# 03_-_CONTROLLER.net
KiCad netlist of a schematic drawn in Altium Designer
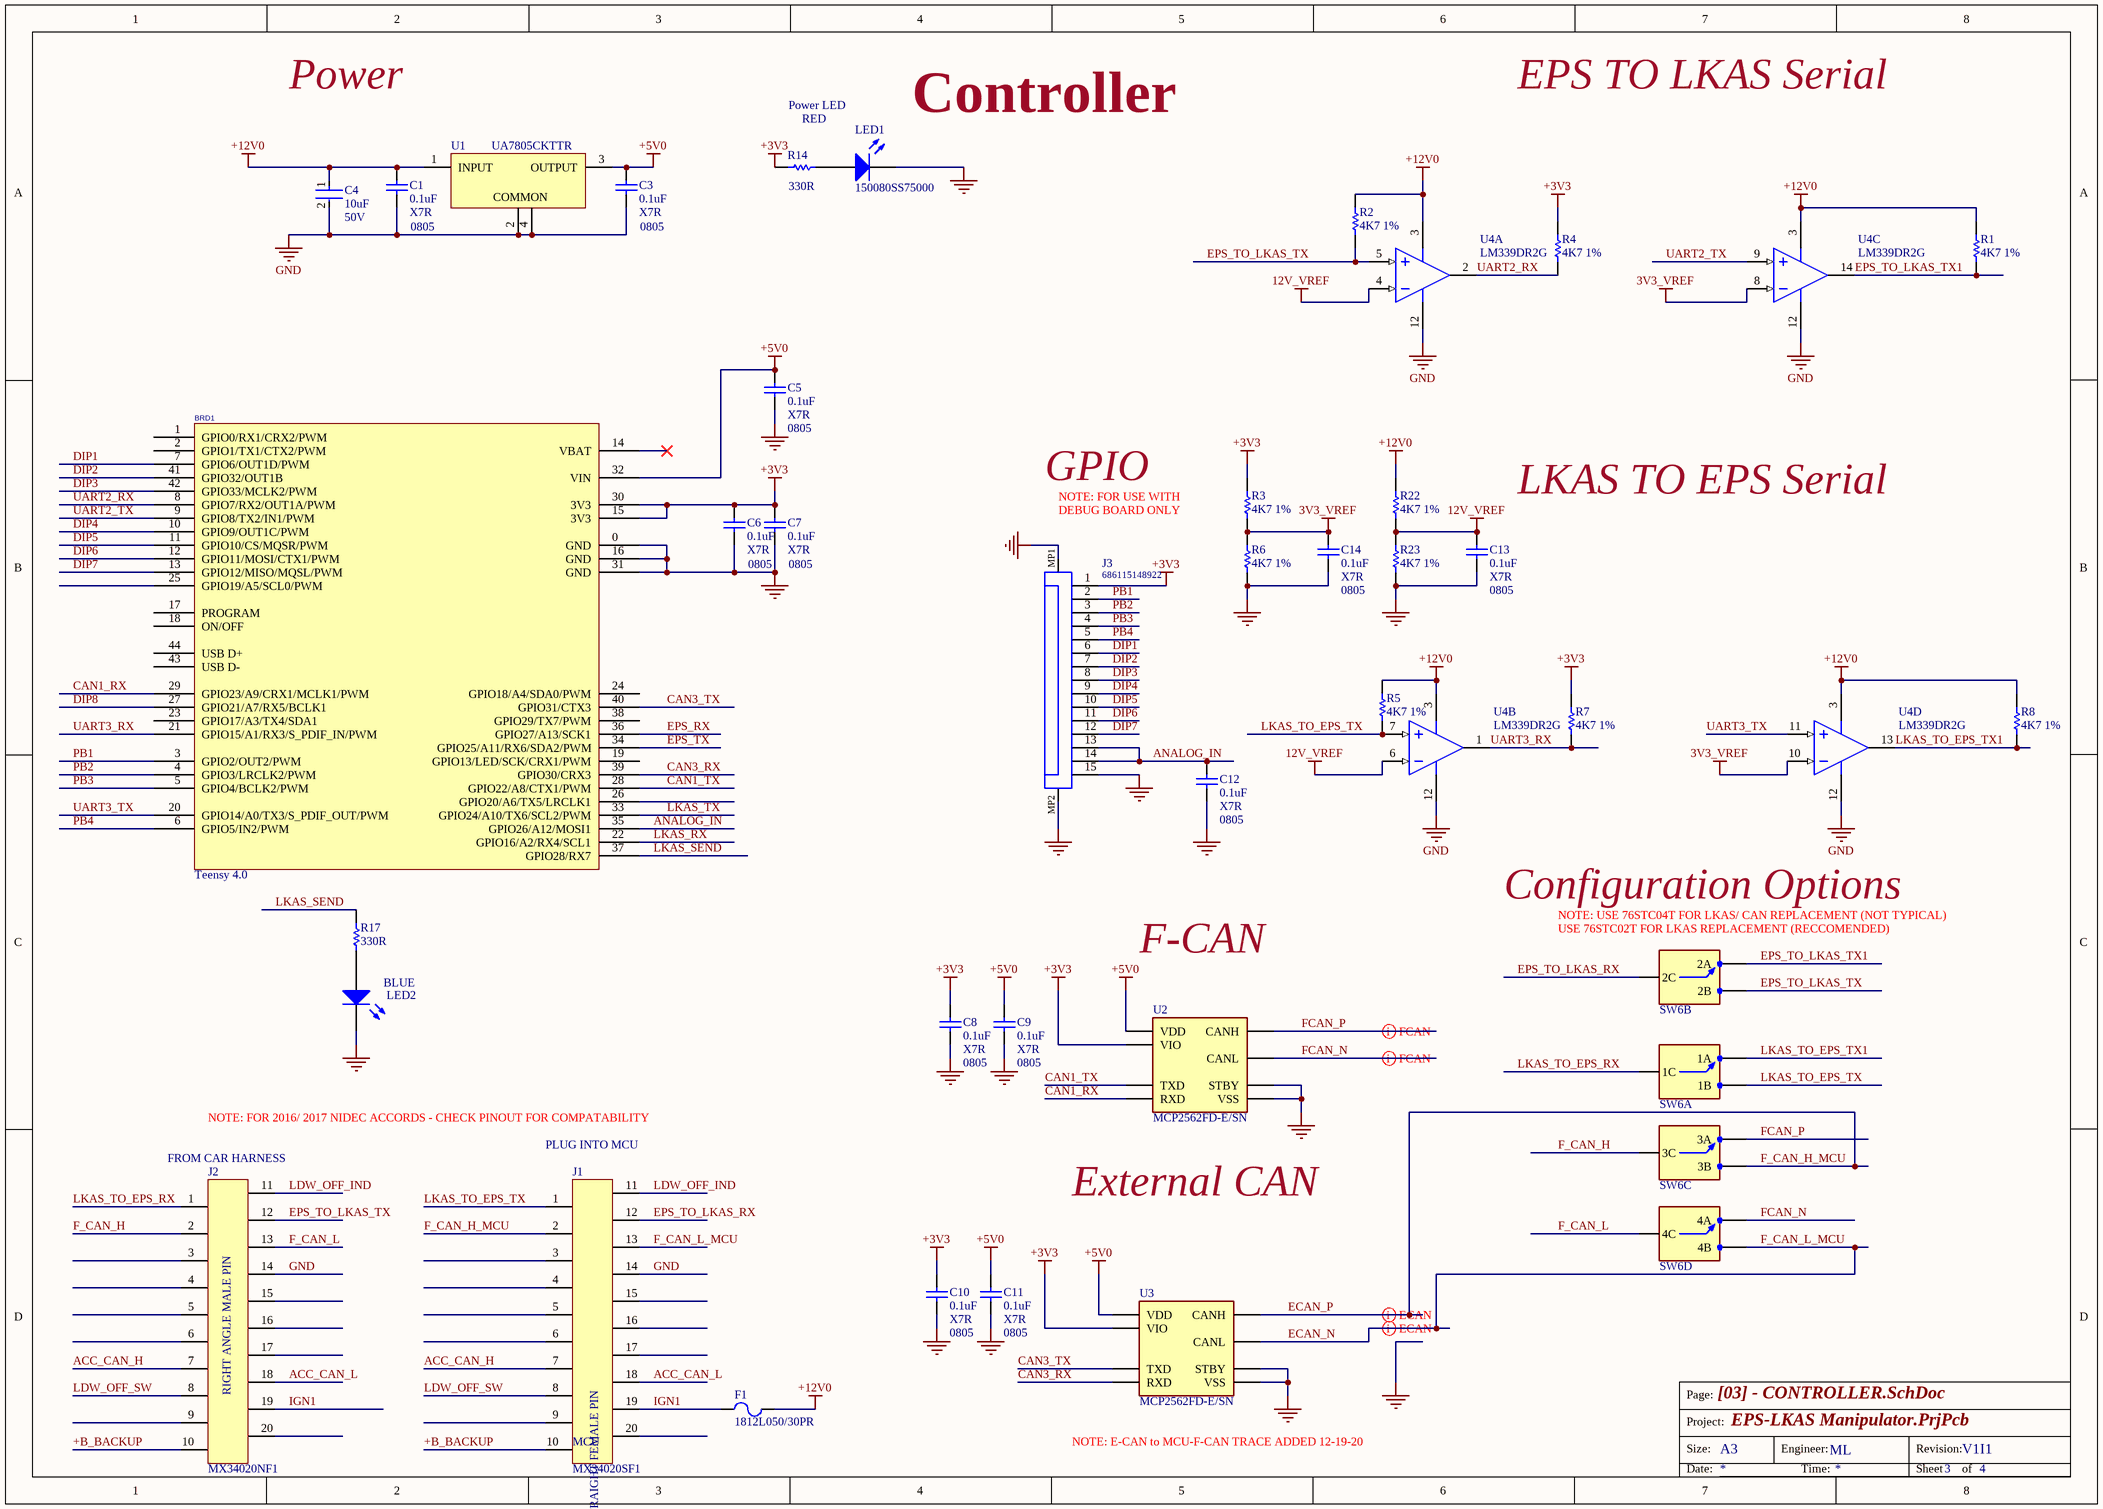
[diagram p0: [03] - CONTROLLER.SchDoc]

(export (version "E")
  (design (tool "Eeschema 10.0.6"))
  (components
    (comp (ref "BRD1")
      (value "Teensy 4.0")
      (footprint "tEENSY 4.0")
      (libsource (lib "EEO440DESIGN") (part "Teensy 4.0"))
    )
    (comp (ref "C1")
      (value "0.1uF")
      (footprint "C0805")
      (description "CAP CER 0.1UF 100V X7R 0805")
      (fields
        (field (name "MANUFACTURER") "Samsung")
        (field (name "MANUFACTURER PART NUMBER") "CL21B104KCFWPNE")
        (field (name "DIELECTRIC") "X7R")
        (field (name "CASE CODE (IMPERIAL)") "0805")
      )
      (libsource (lib "MCU_EPS") (part "CL21B104KCFWPNE"))
    )
    (comp (ref "C3")
      (value "0.1uF")
      (footprint "C0805")
      (description "CAP CER 0.1UF 100V X7R 0805")
      (fields
        (field (name "MANUFACTURER") "Samsung")
        (field (name "MANUFACTURER PART NUMBER") "CL21B104KCFWPNE")
        (field (name "DIELECTRIC") "X7R")
        (field (name "CASE CODE (IMPERIAL)") "0805")
      )
      (libsource (lib "MCU_EPS") (part "CL21B104KCFWPNE"))
    )
    (comp (ref "C4")
      (value "10uF")
      (footprint "FP-CL31-IPC_C")
      (description "CAP CER 10UF 50V X5R 1206")
      (fields
        (field (name "TOLERANCE") "10%")
        (field (name "MANUFACTURER") "Samsung")
        (field (name "VOLTAGE") "50V")
      )
      (libsource (lib "Altium Content Vault") (part "11868f565c42a9108669ba33697ecf6"))
    )
    (comp (ref "C5")
      (value "0.1uF")
      (footprint "C0805")
      (description "CAP CER 0.1UF 100V X7R 0805")
      (fields
        (field (name "MANUFACTURER") "Samsung")
        (field (name "MANUFACTURER PART NUMBER") "CL21B104KCFWPNE")
        (field (name "DIELECTRIC") "X7R")
        (field (name "CASE CODE (IMPERIAL)") "0805")
      )
      (libsource (lib "MCU_EPS") (part "CL21B104KCFWPNE"))
    )
    (comp (ref "C6")
      (value "0.1uF")
      (footprint "C0805")
      (description "CAP CER 0.1UF 100V X7R 0805")
      (fields
        (field (name "MANUFACTURER") "Samsung")
        (field (name "MANUFACTURER PART NUMBER") "CL21B104KCFWPNE")
        (field (name "DIELECTRIC") "X7R")
        (field (name "CASE CODE (IMPERIAL)") "0805")
      )
      (libsource (lib "MCU_EPS") (part "CL21B104KCFWPNE"))
    )
    (comp (ref "C7")
      (value "0.1uF")
      (footprint "C0805")
      (description "CAP CER 0.1UF 100V X7R 0805")
      (fields
        (field (name "MANUFACTURER") "Samsung")
        (field (name "MANUFACTURER PART NUMBER") "CL21B104KCFWPNE")
        (field (name "DIELECTRIC") "X7R")
        (field (name "CASE CODE (IMPERIAL)") "0805")
      )
      (libsource (lib "MCU_EPS") (part "CL21B104KCFWPNE"))
    )
    (comp (ref "C8")
      (value "0.1uF")
      (footprint "C0805")
      (description "CAP CER 0.1UF 100V X7R 0805")
      (fields
        (field (name "MANUFACTURER") "Samsung")
        (field (name "MANUFACTURER PART NUMBER") "CL21B104KCFWPNE")
        (field (name "DIELECTRIC") "X7R")
        (field (name "CASE CODE (IMPERIAL)") "0805")
      )
      (libsource (lib "MCU_EPS") (part "CL21B104KCFWPNE"))
    )
    (comp (ref "C9")
      (value "0.1uF")
      (footprint "C0805")
      (description "CAP CER 0.1UF 100V X7R 0805")
      (fields
        (field (name "MANUFACTURER") "Samsung")
        (field (name "MANUFACTURER PART NUMBER") "CL21B104KCFWPNE")
        (field (name "DIELECTRIC") "X7R")
        (field (name "CASE CODE (IMPERIAL)") "0805")
      )
      (libsource (lib "MCU_EPS") (part "CL21B104KCFWPNE"))
    )
    (comp (ref "C10")
      (value "0.1uF")
      (footprint "C0805")
      (description "CAP CER 0.1UF 100V X7R 0805")
      (fields
        (field (name "MANUFACTURER") "Samsung")
        (field (name "MANUFACTURER PART NUMBER") "CL21B104KCFWPNE")
        (field (name "DIELECTRIC") "X7R")
        (field (name "CASE CODE (IMPERIAL)") "0805")
      )
      (libsource (lib "MCU_EPS") (part "CL21B104KCFWPNE"))
    )
    (comp (ref "C11")
      (value "0.1uF")
      (footprint "C0805")
      (description "CAP CER 0.1UF 100V X7R 0805")
      (fields
        (field (name "MANUFACTURER") "Samsung")
        (field (name "MANUFACTURER PART NUMBER") "CL21B104KCFWPNE")
        (field (name "DIELECTRIC") "X7R")
        (field (name "CASE CODE (IMPERIAL)") "0805")
      )
      (libsource (lib "MCU_EPS") (part "CL21B104KCFWPNE"))
    )
    (comp (ref "C12")
      (value "0.1uF")
      (footprint "C0805")
      (description "CAP CER 0.1UF 100V X7R 0805")
      (fields
        (field (name "MANUFACTURER") "Samsung")
        (field (name "MANUFACTURER PART NUMBER") "CL21B104KCFWPNE")
        (field (name "DIELECTRIC") "X7R")
        (field (name "CASE CODE (IMPERIAL)") "0805")
      )
      (libsource (lib "MCU_EPS") (part "CL21B104KCFWPNE"))
    )
    (comp (ref "C13")
      (value "0.1uF")
      (footprint "C0805")
      (description "CAP CER 0.1UF 100V X7R 0805")
      (fields
        (field (name "MANUFACTURER") "Samsung")
        (field (name "MANUFACTURER PART NUMBER") "CL21B104KCFWPNE")
        (field (name "DIELECTRIC") "X7R")
        (field (name "CASE CODE (IMPERIAL)") "0805")
      )
      (libsource (lib "MCU_EPS") (part "CL21B104KCFWPNE"))
    )
    (comp (ref "C14")
      (value "0.1uF")
      (footprint "C0805")
      (description "CAP CER 0.1UF 100V X7R 0805")
      (fields
        (field (name "MANUFACTURER") "Samsung")
        (field (name "MANUFACTURER PART NUMBER") "CL21B104KCFWPNE")
        (field (name "DIELECTRIC") "X7R")
        (field (name "CASE CODE (IMPERIAL)") "0805")
      )
      (libsource (lib "MCU_EPS") (part "CL21B104KCFWPNE"))
    )
    (comp (ref "F1")
      (value "1812L050/30PR")
      (footprint "LFUS-1812L05030PR_V")
      (description "PTC Resettable Fuse, 0.8 W, 30 V, -40 to 85 degC, 2-Pin SMD, RoHS, Tape and Reel")
      (fields (field (name "MANUFACTURER") "Littelfuse-Inc."))
      (libsource (lib "Altium Content Vault") (part "FUSE-2"))
    )
    (comp (ref "J1")
      (value "MX34020SF1")
      (footprint "MX34020SF1")
      (description "Automotive Connectors Sckt HOUSING 20P")
      (fields (field (name "MANUFACTURER") "JAE Electronics"))
      (libsource (lib "MCU_EPS") (part "MX34020SF1"))
    )
    (comp (ref "J2")
      (value "MX34020NF1")
      (footprint "MX34020NF1")
      (description "JAE MX34 Series, 2.2mm Pitch 20 Way 2 Row Right Angle PCB Header, Solder Termination, 3A")
      (fields (field (name "MANUFACTURER") "JAE Electronics"))
      (libsource (lib "MCU_EPS") (part "MX34020NF1"))
    )
    (comp (ref "J3")
      (value "686115148922")
      (footprint "686115148922")
      (description "SMT ZIF Connectors Hinge Type WR-FPC, Horizontal, Bottom Contact, pitch 1 mm, 15 pins")
      (fields (field (name "MANUFACTURER") "Wurth Elektronik") (field (name "PUBLISHER") "WurthElektronik"))
      (libsource (lib "Altium Content Vault") (part "WE-6861151XXX22-15"))
    )
    (comp (ref "LED1")
      (value "150080SS75000")
      (footprint "0805_A")
      (description "SMD mono-color Chip LED, WL-SMCW, Super Red")
      (fields (field (name "MANUFACTURER") "Wuerth Elektronik"))
      (libsource (lib "Altium Content Vault") (part "WE-LED_K1A2-2"))
    )
    (comp (ref "LED2")
      (value "150080BS75000")
      (footprint "0805_A")
      (description "SMD mono-color Chip LED, WL-SMCW, Blue")
      (fields (field (name "MANUFACTURER") "Wuerth Elektronik"))
      (libsource (lib "Altium Content Vault") (part "WE-LED_K1A2-2"))
    )
    (comp (ref "R1")
      (value "4K7 1%")
      (footprint "RESC0603(1608)_N")
      (description "4K7 0.1W 1% 0603 (1608 Metric)  SMD")
      (fields (field (name "POWER") "0.1 W") (field (name "TOLERANCE") "1 %"))
      (libsource (lib "Altium Content Vault") (part "RES"))
    )
    (comp (ref "R2")
      (value "4K7 1%")
      (footprint "RESC0603(1608)_N")
      (description "4K7 0.1W 1% 0603 (1608 Metric)  SMD")
      (fields (field (name "POWER") "0.1 W") (field (name "TOLERANCE") "1 %"))
      (libsource (lib "Altium Content Vault") (part "RES"))
    )
    (comp (ref "R3")
      (value "4K7 1%")
      (footprint "RESC0603(1608)_N")
      (description "4K7 0.1W 1% 0603 (1608 Metric)  SMD")
      (fields (field (name "POWER") "0.1 W") (field (name "TOLERANCE") "1 %"))
      (libsource (lib "Altium Content Vault") (part "RES"))
    )
    (comp (ref "R4")
      (value "4K7 1%")
      (footprint "RESC0603(1608)_N")
      (description "4K7 0.1W 1% 0603 (1608 Metric)  SMD")
      (fields (field (name "POWER") "0.1 W") (field (name "TOLERANCE") "1 %"))
      (libsource (lib "Altium Content Vault") (part "RES"))
    )
    (comp (ref "R5")
      (value "4K7 1%")
      (footprint "RESC0603(1608)_N")
      (description "4K7 0.1W 1% 0603 (1608 Metric)  SMD")
      (fields (field (name "POWER") "0.1 W") (field (name "TOLERANCE") "1 %"))
      (libsource (lib "Altium Content Vault") (part "RES"))
    )
    (comp (ref "R6")
      (value "4K7 1%")
      (footprint "RESC0603(1608)_N")
      (description "4K7 0.1W 1% 0603 (1608 Metric)  SMD")
      (fields (field (name "POWER") "0.1 W") (field (name "TOLERANCE") "1 %"))
      (libsource (lib "Altium Content Vault") (part "RES"))
    )
    (comp (ref "R7")
      (value "4K7 1%")
      (footprint "RESC0603(1608)_N")
      (description "4K7 0.1W 1% 0603 (1608 Metric)  SMD")
      (fields (field (name "POWER") "0.1 W") (field (name "TOLERANCE") "1 %"))
      (libsource (lib "Altium Content Vault") (part "RES"))
    )
    (comp (ref "R8")
      (value "4K7 1%")
      (footprint "RESC0603(1608)_N")
      (description "4K7 0.1W 1% 0603 (1608 Metric)  SMD")
      (fields (field (name "POWER") "0.1 W") (field (name "TOLERANCE") "1 %"))
      (libsource (lib "Altium Content Vault") (part "RES"))
    )
    (comp (ref "R14")
      (value "330R")
      (footprint "RESC2013X50X30NL20T20")
      (fields (field (name "MANUFACTURER") "Vishay Dale") (field (name "PART NUMBER") "CRCW0805330RFKEA"))
      (libsource (lib "Altium Content Vault") (part "RES"))
    )
    (comp (ref "R17")
      (value "330R")
      (footprint "RESC2013X50X30NL20T20")
      (fields (field (name "MANUFACTURER") "Vishay Dale") (field (name "PART NUMBER") "CRCW0805330RFKEA"))
      (libsource (lib "Altium Content Vault") (part "RES"))
    )
    (comp (ref "R22")
      (value "4K7 1%")
      (footprint "RESC0603(1608)_N")
      (description "4K7 0.1W 1% 0603 (1608 Metric)  SMD")
      (fields (field (name "POWER") "0.1 W") (field (name "TOLERANCE") "1 %"))
      (libsource (lib "Altium Content Vault") (part "RES"))
    )
    (comp (ref "R23")
      (value "4K7 1%")
      (footprint "RESC0603(1608)_N")
      (description "4K7 0.1W 1% 0603 (1608 Metric)  SMD")
      (fields (field (name "POWER") "0.1 W") (field (name "TOLERANCE") "1 %"))
      (libsource (lib "Altium Content Vault") (part "RES"))
    )
    (comp (ref "SW6")
      (value "76STC04T")
      (footprint "76STC04T")
      (description "SWITCH TOGGLE DIP SPDT 150MA 30V\r\nWIRED:\r\n1  2  3  4   5   6\r\n7  8  9  10 11 12")
      (fields (field (name "MANUFACTURER") "Grayhill"))
      (libsource (lib "MCU_EPS") (part "76STC04T"))
    )
    (comp (ref "U1")
      (value "UA7805CKTTR")
      (footprint "KTT0003A_V")
      (fields (field (name "TOLERANCE") "1%"))
      (libsource (lib "Altium Content Vault") (part "TI-UA78XX-KTT-3"))
    )
    (comp (ref "U2")
      (value "MCP2562FD-E/SN")
      (footprint "MCP2561")
      (description "8 SOIC 3.90mm(.150in) TUBECAN Flexible Data Rate Transceiver")
      (fields (field (name "MANUFACTURER") "Microchip"))
      (libsource (lib "MCU_EPS") (part "MCP2562FD-E/SN"))
    )
    (comp (ref "U3")
      (value "MCP2562FD-E/SN")
      (footprint "MCP2561")
      (description "8 SOIC 3.90mm(.150in) TUBECAN Flexible Data Rate Transceiver")
      (fields (field (name "MANUFACTURER") "Microchip"))
      (libsource (lib "MCU_EPS") (part "MCP2562FD-E/SN"))
    )
    (comp (ref "U4")
      (value "LM339DR2G")
      (footprint "ONSC-SOIC-14-751A-03_V")
      (description "Single Supply Quad Comparators, 0 to 70 degC, 14-Pin SOIC, Pb-Free, Tape and Reel")
      (fields (field (name "MANUFACTURER") "On Semiconductor"))
      (libsource (lib "Altium Content Vault") (part "ONSC-LM239_LM339_LM2901_NCV2901_MC3302_LMV339-14"))
    )
  )
  (nets
    (net (code "1") (name "+3V3") (class "Default")
      (node (ref "BRD1") (pin "15") (pinfunction "3V3_15") (pintype "passive"))
      (node (ref "BRD1") (pin "30") (pinfunction "3V3_30") (pintype "passive"))
      (node (ref "C10") (pin "2") (pinfunction "2_2") (pintype "passive"))
      (node (ref "C6") (pin "2") (pinfunction "2_2") (pintype "passive"))
      (node (ref "C7") (pin "2") (pinfunction "2_2") (pintype "passive"))
      (node (ref "C8") (pin "2") (pinfunction "2_2") (pintype "passive"))
      (node (ref "J3") (pin "1") (pinfunction "1_1") (pintype "passive"))
      (node (ref "R14") (pin "1") (pinfunction "1_1") (pintype "passive"))
      (node (ref "R3") (pin "2") (pinfunction "2_2") (pintype "passive"))
      (node (ref "R4") (pin "2") (pinfunction "2_2") (pintype "passive"))
      (node (ref "R7") (pin "2") (pinfunction "2_2") (pintype "passive"))
      (node (ref "U2") (pin "5") (pinfunction "VIO_5") (pintype "passive"))
      (node (ref "U3") (pin "5") (pinfunction "VIO_5") (pintype "passive"))
    )
    (net (code "2") (name "+5V0") (class "Default")
      (node (ref "BRD1") (pin "32") (pinfunction "VIN_32") (pintype "passive"))
      (node (ref "C11") (pin "2") (pinfunction "2_2") (pintype "passive"))
      (node (ref "C3") (pin "2") (pinfunction "2_2") (pintype "passive"))
      (node (ref "C5") (pin "2") (pinfunction "2_2") (pintype "passive"))
      (node (ref "C9") (pin "2") (pinfunction "2_2") (pintype "passive"))
      (node (ref "U1") (pin "3") (pinfunction "OUTPUT_3") (pintype "power_in"))
      (node (ref "U2") (pin "3") (pinfunction "VDD_3") (pintype "passive"))
      (node (ref "U3") (pin "3") (pinfunction "VDD_3") (pintype "passive"))
    )
    (net (code "3") (name "+12V0") (class "Default")
      (node (ref "C1") (pin "2") (pinfunction "2_2") (pintype "passive"))
      (node (ref "C4") (pin "1") (pinfunction "1_1") (pintype "passive"))
      (node (ref "F1") (pin "2") (pinfunction "2_2") (pintype "passive"))
      (node (ref "R1") (pin "2") (pinfunction "2_2") (pintype "passive"))
      (node (ref "R2") (pin "2") (pinfunction "2_2") (pintype "passive"))
      (node (ref "R22") (pin "2") (pinfunction "2_2") (pintype "passive"))
      (node (ref "R5") (pin "2") (pinfunction "2_2") (pintype "passive"))
      (node (ref "R8") (pin "2") (pinfunction "2_2") (pintype "passive"))
      (node (ref "U1") (pin "1") (pinfunction "INPUT_1") (pintype "power_in"))
      (node (ref "U4") (pin "3") (pinfunction "VCC_3") (pintype "power_in"))
    )
    (net (code "4") (name "/+B_BACKUP") (class "Default")
      (node (ref "J1") (pin "10") (pinfunction "10_10") (pintype "passive"))
      (node (ref "J2") (pin "10") (pinfunction "10_10") (pintype "passive"))
    )
    (net (code "6") (name "/ACC_CAN_H") (class "Default")
      (node (ref "J1") (pin "7") (pinfunction "7_7") (pintype "passive"))
      (node (ref "J2") (pin "7") (pinfunction "7_7") (pintype "passive"))
    )
    (net (code "7") (name "/ACC_CAN_L") (class "Default")
      (node (ref "J1") (pin "18") (pinfunction "18_18") (pintype "passive"))
      (node (ref "J2") (pin "18") (pinfunction "18_18") (pintype "passive"))
    )
    (net (code "8") (name "/ANALOG_IN") (class "Default")
      (node (ref "BRD1") (pin "35") (pinfunction "GPIO26/A12/MOSI1_35") (pintype "passive"))
      (node (ref "C12") (pin "2") (pinfunction "2_2") (pintype "passive"))
      (node (ref "J3") (pin "13") (pinfunction "13_13") (pintype "passive"))
      (node (ref "J3") (pin "14") (pinfunction "14_14") (pintype "passive"))
    )
    (net (code "9") (name "/CAN1_RX") (class "Default")
      (node (ref "BRD1") (pin "29") (pinfunction "GPIO23/A9/CRX1/MCLK1/PWM_29") (pintype "passive"))
      (node (ref "U2") (pin "4") (pinfunction "RXD_4") (pintype "passive"))
    )
    (net (code "10") (name "/CAN1_TX") (class "Default")
      (node (ref "BRD1") (pin "28") (pinfunction "GPIO22/A8/CTX1/PWM_28") (pintype "passive"))
      (node (ref "U2") (pin "1") (pinfunction "TXD_1") (pintype "passive"))
    )
    (net (code "11") (name "/CAN3_RX") (class "Default")
      (node (ref "BRD1") (pin "39") (pinfunction "GPIO30/CRX3_39") (pintype "passive"))
      (node (ref "U3") (pin "4") (pinfunction "RXD_4") (pintype "passive"))
    )
    (net (code "12") (name "/CAN3_TX") (class "Default")
      (node (ref "BRD1") (pin "40") (pinfunction "GPIO31/CTX3_40") (pintype "passive"))
      (node (ref "U3") (pin "1") (pinfunction "TXD_1") (pintype "passive"))
    )
    (net (code "13") (name "/DIP1") (class "Default")
      (node (ref "BRD1") (pin "7") (pinfunction "GPIO6/OUT1D/PWM_7") (pintype "passive"))
      (node (ref "J3") (pin "6") (pinfunction "6_6") (pintype "passive"))
    )
    (net (code "14") (name "/DIP2") (class "Default")
      (node (ref "BRD1") (pin "41") (pinfunction "GPIO32/OUT1B_41") (pintype "passive"))
      (node (ref "J3") (pin "7") (pinfunction "7_7") (pintype "passive"))
    )
    (net (code "15") (name "/DIP3") (class "Default")
      (node (ref "BRD1") (pin "42") (pinfunction "GPIO33/MCLK2/PWM_42") (pintype "passive"))
      (node (ref "J3") (pin "8") (pinfunction "8_8") (pintype "passive"))
    )
    (net (code "16") (name "/DIP4") (class "Default")
      (node (ref "BRD1") (pin "10") (pinfunction "GPIO9/OUT1C/PWM_10") (pintype "passive"))
      (node (ref "J3") (pin "9") (pinfunction "9_9") (pintype "passive"))
    )
    (net (code "17") (name "/DIP5") (class "Default")
      (node (ref "BRD1") (pin "11") (pinfunction "GPIO10/CS/MQSR/PWM_11") (pintype "passive"))
      (node (ref "J3") (pin "10") (pinfunction "10_10") (pintype "passive"))
    )
    (net (code "18") (name "/DIP6") (class "Default")
      (node (ref "BRD1") (pin "12") (pinfunction "GPIO11/MOSI/CTX1/PWM_12") (pintype "passive"))
      (node (ref "J3") (pin "11") (pinfunction "11_11") (pintype "passive"))
    )
    (net (code "19") (name "/DIP7") (class "Default")
      (node (ref "BRD1") (pin "13") (pinfunction "GPIO12/MISO/MQSL/PWM_13") (pintype "passive"))
      (node (ref "J3") (pin "12") (pinfunction "12_12") (pintype "passive"))
    )
    (net (code "20") (name "/DIP8") (class "Default")
      (node (ref "BRD1") (pin "27") (pinfunction "GPIO21/A7/RX5/BCLK1_27") (pintype "passive"))
    )
    (net (code "21") (name "/ECAN_N") (class "Default")
      (node (ref "J1") (pin "13") (pinfunction "13_13") (pintype "passive"))
      (node (ref "SW6") (pin "4B") (pinfunction "4B_4B") (pintype "passive"))
      (node (ref "U3") (pin "6") (pinfunction "CANL_6") (pintype "passive"))
    )
    (net (code "22") (name "/ECAN_P") (class "Default")
      (node (ref "J1") (pin "2") (pinfunction "2_2") (pintype "passive"))
      (node (ref "SW6") (pin "3B") (pinfunction "3B_3B") (pintype "passive"))
      (node (ref "U3") (pin "7") (pinfunction "CANH_7") (pintype "passive"))
    )
    (net (code "23") (name "/EPS_RX") (class "Default")
      (node (ref "BRD1") (pin "36") (pinfunction "GPIO27/A13/SCK1_36") (pintype "passive"))
    )
    (net (code "24") (name "/EPS_TO_LKAS_RX") (class "Default")
      (node (ref "J1") (pin "12") (pinfunction "12_12") (pintype "passive"))
      (node (ref "SW6") (pin "C2") (pinfunction "2C_C2") (pintype "passive"))
    )
    (net (code "25") (name "/EPS_TO_LKAS_TX") (class "Default")
      (node (ref "J2") (pin "12") (pinfunction "12_12") (pintype "passive"))
      (node (ref "R2") (pin "1") (pinfunction "1_1") (pintype "passive"))
      (node (ref "SW6") (pin "2B") (pinfunction "2B_2B") (pintype "passive"))
      (node (ref "U4") (pin "5") (pinfunction "IN1+_5") (pintype "input"))
    )
    (net (code "26") (name "/EPS_TO_LKAS_TX1") (class "Default")
      (node (ref "R1") (pin "1") (pinfunction "1_1") (pintype "passive"))
      (node (ref "SW6") (pin "2A") (pinfunction "2A_2A") (pintype "passive"))
      (node (ref "U4") (pin "14") (pinfunction "OUT3_14") (pintype "open_collector"))
    )
    (net (code "27") (name "/EPS_TX") (class "Default")
      (node (ref "BRD1") (pin "34") (pinfunction "GPIO25/A11/RX6/SDA2/PWM_34") (pintype "passive"))
    )
    (net (code "28") (name "/FCAN_N") (class "Default")
      (node (ref "SW6") (pin "4A") (pinfunction "4A_4A") (pintype "passive"))
      (node (ref "U2") (pin "6") (pinfunction "CANL_6") (pintype "passive"))
    )
    (net (code "29") (name "/FCAN_P") (class "Default")
      (node (ref "SW6") (pin "3A") (pinfunction "3A_3A") (pintype "passive"))
      (node (ref "U2") (pin "7") (pinfunction "CANH_7") (pintype "passive"))
    )
    (net (code "30") (name "/F_CAN_H") (class "Default")
      (node (ref "J2") (pin "2") (pinfunction "2_2") (pintype "passive"))
      (node (ref "SW6") (pin "C3") (pinfunction "3C_C3") (pintype "passive"))
    )
    (net (code "31") (name "/F_CAN_L") (class "Default")
      (node (ref "J2") (pin "13") (pinfunction "13_13") (pintype "passive"))
      (node (ref "SW6") (pin "C4") (pinfunction "4C_C4") (pintype "passive"))
    )
    (net (code "32") (name "/IGN1") (class "Default")
      (node (ref "F1") (pin "1") (pinfunction "1_1") (pintype "passive"))
      (node (ref "J1") (pin "19") (pinfunction "19_19") (pintype "passive"))
      (node (ref "J2") (pin "19") (pinfunction "19_19") (pintype "passive"))
    )
    (net (code "33") (name "/LDW_OFF_IND") (class "Default")
      (node (ref "J1") (pin "11") (pinfunction "11_11") (pintype "passive"))
      (node (ref "J2") (pin "11") (pinfunction "11_11") (pintype "passive"))
    )
    (net (code "34") (name "/LDW_OFF_SW") (class "Default")
      (node (ref "J1") (pin "8") (pinfunction "8_8") (pintype "passive"))
      (node (ref "J2") (pin "8") (pinfunction "8_8") (pintype "passive"))
    )
    (net (code "35") (name "/LKAS_RX") (class "Default")
      (node (ref "BRD1") (pin "22") (pinfunction "GPIO16/A2/RX4/SCL1_22") (pintype "passive"))
    )
    (net (code "36") (name "/LKAS_SEND") (class "Default")
      (node (ref "BRD1") (pin "37") (pinfunction "GPIO28/RX7_37") (pintype "passive"))
      (node (ref "R17") (pin "2") (pinfunction "2_2") (pintype "passive"))
    )
    (net (code "37") (name "/LKAS_TO_EPS_RX") (class "Default")
      (node (ref "J2") (pin "1") (pinfunction "1_1") (pintype "passive"))
      (node (ref "SW6") (pin "C1") (pinfunction "1C_C1") (pintype "passive"))
    )
    (net (code "38") (name "/LKAS_TO_EPS_TX") (class "Default")
      (node (ref "J1") (pin "1") (pinfunction "1_1") (pintype "passive"))
      (node (ref "R5") (pin "1") (pinfunction "1_1") (pintype "passive"))
      (node (ref "SW6") (pin "1B") (pinfunction "1B_1B") (pintype "passive"))
      (node (ref "U4") (pin "7") (pinfunction "IN2+_7") (pintype "input"))
    )
    (net (code "39") (name "/LKAS_TO_EPS_TX1") (class "Default")
      (node (ref "R8") (pin "1") (pinfunction "1_1") (pintype "passive"))
      (node (ref "SW6") (pin "1A") (pinfunction "1A_1A") (pintype "passive"))
      (node (ref "U4") (pin "13") (pinfunction "OUT4_13") (pintype "open_collector"))
    )
    (net (code "40") (name "/LKAS_TX") (class "Default")
      (node (ref "BRD1") (pin "33") (pinfunction "GPIO24/A10/TX6/SCL2/PWM_33") (pintype "passive"))
    )
    (net (code "41") (name "/PB1") (class "Default")
      (node (ref "BRD1") (pin "3") (pinfunction "GPIO2/OUT2/PWM_3") (pintype "passive"))
      (node (ref "J3") (pin "2") (pinfunction "2_2") (pintype "passive"))
    )
    (net (code "42") (name "/PB2") (class "Default")
      (node (ref "BRD1") (pin "4") (pinfunction "GPIO3/LRCLK2/PWM_4") (pintype "passive"))
      (node (ref "J3") (pin "3") (pinfunction "3_3") (pintype "passive"))
    )
    (net (code "43") (name "/PB3") (class "Default")
      (node (ref "BRD1") (pin "5") (pinfunction "GPIO4/BCLK2/PWM_5") (pintype "passive"))
      (node (ref "J3") (pin "4") (pinfunction "4_4") (pintype "passive"))
    )
    (net (code "44") (name "/PB4") (class "Default")
      (node (ref "BRD1") (pin "6") (pinfunction "GPIO5/IN2/PWM_6") (pintype "passive"))
      (node (ref "J3") (pin "5") (pinfunction "5_5") (pintype "passive"))
    )
    (net (code "45") (name "/UART2_RX") (class "Default")
      (node (ref "BRD1") (pin "8") (pinfunction "GPIO7/RX2/OUT1A/PWM_8") (pintype "passive"))
      (node (ref "R4") (pin "1") (pinfunction "1_1") (pintype "passive"))
      (node (ref "U4") (pin "2") (pinfunction "OUT1_2") (pintype "open_collector"))
    )
    (net (code "46") (name "/UART2_TX") (class "Default")
      (node (ref "BRD1") (pin "9") (pinfunction "GPIO8/TX2/IN1/PWM_9") (pintype "passive"))
      (node (ref "U4") (pin "9") (pinfunction "IN3+_9") (pintype "input"))
    )
    (net (code "47") (name "/UART3_RX") (class "Default")
      (node (ref "BRD1") (pin "21") (pinfunction "GPIO15/A1/RX3/S_PDIF_IN/PWM_21") (pintype "passive"))
      (node (ref "R7") (pin "1") (pinfunction "1_1") (pintype "passive"))
      (node (ref "U4") (pin "1") (pinfunction "OUT2_1") (pintype "open_collector"))
    )
    (net (code "48") (name "/UART3_TX") (class "Default")
      (node (ref "BRD1") (pin "20") (pinfunction "GPIO14/A0/TX3/S_PDIF_OUT/PWM_20") (pintype "passive"))
      (node (ref "U4") (pin "11") (pinfunction "IN4+_11") (pintype "input"))
    )
    (net (code "49") (name "3V3_VREF") (class "Default")
      (node (ref "C14") (pin "2") (pinfunction "2_2") (pintype "passive"))
      (node (ref "R3") (pin "1") (pinfunction "1_1") (pintype "passive"))
      (node (ref "R6") (pin "2") (pinfunction "2_2") (pintype "passive"))
      (node (ref "U4") (pin "10") (pinfunction "IN4-_10") (pintype "input"))
      (node (ref "U4") (pin "8") (pinfunction "IN3-_8") (pintype "input"))
    )
    (net (code "50") (name "12V_VREF") (class "Default")
      (node (ref "C13") (pin "2") (pinfunction "2_2") (pintype "passive"))
      (node (ref "R22") (pin "1") (pinfunction "1_1") (pintype "passive"))
      (node (ref "R23") (pin "2") (pinfunction "2_2") (pintype "passive"))
      (node (ref "U4") (pin "4") (pinfunction "IN1-_4") (pintype "input"))
      (node (ref "U4") (pin "6") (pinfunction "IN2-_6") (pintype "input"))
    )
    (net (code "51") (name "GND") (class "Default")
      (node (ref "BRD1") (pin "0") (pinfunction "GND_0") (pintype "passive"))
      (node (ref "BRD1") (pin "16") (pinfunction "GND_16") (pintype "passive"))
      (node (ref "BRD1") (pin "31") (pinfunction "GND_31") (pintype "passive"))
      (node (ref "C1") (pin "1") (pinfunction "1_1") (pintype "passive"))
      (node (ref "C10") (pin "1") (pinfunction "1_1") (pintype "passive"))
      (node (ref "C11") (pin "1") (pinfunction "1_1") (pintype "passive"))
      (node (ref "C12") (pin "1") (pinfunction "1_1") (pintype "passive"))
      (node (ref "C13") (pin "1") (pinfunction "1_1") (pintype "passive"))
      (node (ref "C14") (pin "1") (pinfunction "1_1") (pintype "passive"))
      (node (ref "C3") (pin "1") (pinfunction "1_1") (pintype "passive"))
      (node (ref "C4") (pin "2") (pinfunction "2_2") (pintype "passive"))
      (node (ref "C5") (pin "1") (pinfunction "1_1") (pintype "passive"))
      (node (ref "C6") (pin "1") (pinfunction "1_1") (pintype "passive"))
      (node (ref "C7") (pin "1") (pinfunction "1_1") (pintype "passive"))
      (node (ref "C8") (pin "1") (pinfunction "1_1") (pintype "passive"))
      (node (ref "C9") (pin "1") (pinfunction "1_1") (pintype "passive"))
      (node (ref "J1") (pin "14") (pinfunction "14_14") (pintype "passive"))
      (node (ref "J2") (pin "14") (pinfunction "14_14") (pintype "passive"))
      (node (ref "J3") (pin "15") (pinfunction "15_15") (pintype "passive"))
      (node (ref "J3") (pin "MP1") (pinfunction "MP1_MP1") (pintype "passive"))
      (node (ref "J3") (pin "MP2") (pinfunction "MP2_MP2") (pintype "passive"))
      (node (ref "LED1") (pin "1") (pinfunction "K_1") (pintype "passive"))
      (node (ref "LED2") (pin "1") (pinfunction "K_1") (pintype "passive"))
      (node (ref "R23") (pin "1") (pinfunction "1_1") (pintype "passive"))
      (node (ref "R6") (pin "1") (pinfunction "1_1") (pintype "passive"))
      (node (ref "U1") (pin "2") (pinfunction "COMMON_2") (pintype "power_in"))
      (node (ref "U1") (pin "4") (pinfunction "COMMON_4") (pintype "power_in"))
      (node (ref "U2") (pin "2") (pinfunction "VSS_2") (pintype "passive"))
      (node (ref "U2") (pin "8") (pinfunction "STBY_8") (pintype "passive"))
      (node (ref "U3") (pin "2") (pinfunction "VSS_2") (pintype "passive"))
      (node (ref "U3") (pin "8") (pinfunction "STBY_8") (pintype "passive"))
      (node (ref "U4") (pin "12") (pinfunction "GND_12") (pintype "power_in"))
    )
    (net (code "52") (name "Net-(LED1-A)") (class "Default")
      (node (ref "LED1") (pin "2") (pinfunction "A_2") (pintype "passive"))
      (node (ref "R14") (pin "2") (pinfunction "2_2") (pintype "passive"))
    )
    (net (code "53") (name "Net-(LED2-A)") (class "Default")
      (node (ref "LED2") (pin "2") (pinfunction "A_2") (pintype "passive"))
      (node (ref "R17") (pin "1") (pinfunction "1_1") (pintype "passive"))
    )
    (net (code "54") (name "unconnected-(BRD1-GPIO0{slash}RX1{slash}CRX2{slash}PWM-Pad1)") (class "Default")
      (node (ref "BRD1") (pin "1") (pinfunction "GPIO0/RX1/CRX2/PWM_1") (pintype "passive"))
    )
    (net (code "55") (name "unconnected-(BRD1-GPIO1{slash}TX1{slash}CTX2{slash}PWM-Pad2)") (class "Default")
      (node (ref "BRD1") (pin "2") (pinfunction "GPIO1/TX1/CTX2/PWM_2") (pintype "passive"))
    )
    (net (code "56") (name "unconnected-(BRD1-GPIO13{slash}LED{slash}SCK{slash}CRX1{slash}PWM-Pad19)") (class "Default")
      (node (ref "BRD1") (pin "19") (pinfunction "GPIO13/LED/SCK/CRX1/PWM_19") (pintype "passive"))
    )
    (net (code "57") (name "unconnected-(BRD1-GPIO17{slash}A3{slash}TX4{slash}SDA1-Pad23)") (class "Default")
      (node (ref "BRD1") (pin "23") (pinfunction "GPIO17/A3/TX4/SDA1_23") (pintype "passive"))
    )
    (net (code "58") (name "unconnected-(BRD1-GPIO18{slash}A4{slash}SDA0{slash}PWM-Pad24)") (class "Default")
      (node (ref "BRD1") (pin "24") (pinfunction "GPIO18/A4/SDA0/PWM_24") (pintype "passive"))
    )
    (net (code "59") (name "unconnected-(BRD1-GPIO19{slash}A5{slash}SCL0{slash}PWM-Pad25)") (class "Default")
      (node (ref "BRD1") (pin "25") (pinfunction "GPIO19/A5/SCL0/PWM_25") (pintype "passive"))
    )
    (net (code "60") (name "unconnected-(BRD1-GPIO20{slash}A6{slash}TX5{slash}LRCLK1-Pad26)") (class "Default")
      (node (ref "BRD1") (pin "26") (pinfunction "GPIO20/A6/TX5/LRCLK1_26") (pintype "passive"))
    )
    (net (code "61") (name "unconnected-(BRD1-GPIO29{slash}TX7{slash}PWM-Pad38)") (class "Default")
      (node (ref "BRD1") (pin "38") (pinfunction "GPIO29/TX7/PWM_38") (pintype "passive"))
    )
    (net (code "62") (name "unconnected-(BRD1-ON{slash}OFF-Pad18)") (class "Default")
      (node (ref "BRD1") (pin "18") (pinfunction "ON/OFF_18") (pintype "passive"))
    )
    (net (code "63") (name "unconnected-(BRD1-PROGRAM-Pad17)") (class "Default")
      (node (ref "BRD1") (pin "17") (pinfunction "PROGRAM_17") (pintype "passive"))
    )
    (net (code "64") (name "unconnected-(BRD1-USB_D+-Pad44)") (class "Default")
      (node (ref "BRD1") (pin "44") (pinfunction "USB_D+_44") (pintype "passive"))
    )
    (net (code "65") (name "unconnected-(BRD1-USB_D--Pad43)") (class "Default")
      (node (ref "BRD1") (pin "43") (pinfunction "USB_D-_43") (pintype "passive"))
    )
    (net (code "66") (name "unconnected-(BRD1-VBAT-Pad14)") (class "Default")
      (node (ref "BRD1") (pin "14") (pinfunction "VBAT_14") (pintype "passive+no_connect"))
    )
    (net (code "67") (name "unconnected-(J1-Pad3)") (class "Default")
      (node (ref "J1") (pin "3") (pinfunction "3_3") (pintype "passive"))
    )
    (net (code "68") (name "unconnected-(J1-Pad4)") (class "Default")
      (node (ref "J1") (pin "4") (pinfunction "4_4") (pintype "passive"))
    )
    (net (code "69") (name "unconnected-(J1-Pad5)") (class "Default")
      (node (ref "J1") (pin "5") (pinfunction "5_5") (pintype "passive"))
    )
    (net (code "70") (name "unconnected-(J1-Pad6)") (class "Default")
      (node (ref "J1") (pin "6") (pinfunction "6_6") (pintype "passive"))
    )
    (net (code "71") (name "unconnected-(J1-Pad9)") (class "Default")
      (node (ref "J1") (pin "9") (pinfunction "9_9") (pintype "passive"))
    )
    (net (code "72") (name "unconnected-(J1-Pad15)") (class "Default")
      (node (ref "J1") (pin "15") (pinfunction "15_15") (pintype "passive"))
    )
    (net (code "73") (name "unconnected-(J1-Pad16)") (class "Default")
      (node (ref "J1") (pin "16") (pinfunction "16_16") (pintype "passive"))
    )
    (net (code "74") (name "unconnected-(J1-Pad17)") (class "Default")
      (node (ref "J1") (pin "17") (pinfunction "17_17") (pintype "passive"))
    )
    (net (code "75") (name "unconnected-(J1-Pad20)") (class "Default")
      (node (ref "J1") (pin "20") (pinfunction "20_20") (pintype "passive"))
    )
    (net (code "76") (name "unconnected-(J2-Pad3)") (class "Default")
      (node (ref "J2") (pin "3") (pinfunction "3_3") (pintype "passive"))
    )
    (net (code "77") (name "unconnected-(J2-Pad4)") (class "Default")
      (node (ref "J2") (pin "4") (pinfunction "4_4") (pintype "passive"))
    )
    (net (code "78") (name "unconnected-(J2-Pad5)") (class "Default")
      (node (ref "J2") (pin "5") (pinfunction "5_5") (pintype "passive"))
    )
    (net (code "79") (name "unconnected-(J2-Pad6)") (class "Default")
      (node (ref "J2") (pin "6") (pinfunction "6_6") (pintype "passive"))
    )
    (net (code "80") (name "unconnected-(J2-Pad9)") (class "Default")
      (node (ref "J2") (pin "9") (pinfunction "9_9") (pintype "passive"))
    )
    (net (code "81") (name "unconnected-(J2-Pad15)") (class "Default")
      (node (ref "J2") (pin "15") (pinfunction "15_15") (pintype "passive"))
    )
    (net (code "82") (name "unconnected-(J2-Pad16)") (class "Default")
      (node (ref "J2") (pin "16") (pinfunction "16_16") (pintype "passive"))
    )
    (net (code "83") (name "unconnected-(J2-Pad17)") (class "Default")
      (node (ref "J2") (pin "17") (pinfunction "17_17") (pintype "passive"))
    )
    (net (code "84") (name "unconnected-(J2-Pad20)") (class "Default")
      (node (ref "J2") (pin "20") (pinfunction "20_20") (pintype "passive"))
    )
  )
)
